# ADCIN_ACcoupled_ADT1-1WT.net
KiCad netlist of a schematic drawn in Altium Designer
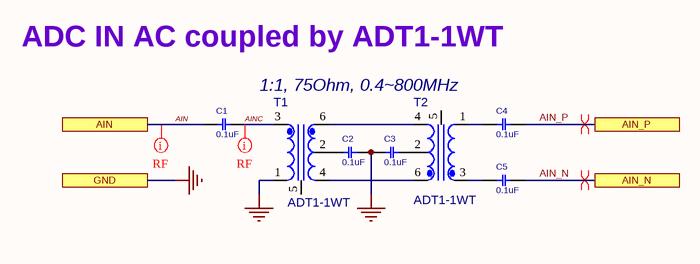
[diagram p0: ADCIN_ACcoupled_ADT1-1WT.SchDoc]

(export (version "E")
  (design (tool "Eeschema 10.0.6"))
  (components
    (comp (ref "C1")
      (value "0.1uF")
      (footprint "C0402")
      (description "CAP, MLCC, 100nF, 50V, X7R, 10%, 0402C")
      (fields (field (name "MANF_P#") "GCM155R71H104KE02D") (field (name "MANF") "Murata"))
      (libsource (lib "mlcc_smd_passive") (part "CAP_SMD_MLCC_100n50TDK"))
    )
    (comp (ref "C2")
      (value "0.1uF")
      (footprint "C0402")
      (description "CAP, MLCC, 100nF, 50V, X7R, 10%, 0402C")
      (fields (field (name "MANF_P#") "GCM155R71H104KE02D") (field (name "MANF") "Murata"))
      (libsource (lib "mlcc_smd_passive") (part "CAP_SMD_MLCC_100n50TDK"))
    )
    (comp (ref "C3")
      (value "0.1uF")
      (footprint "C0402")
      (description "CAP, MLCC, 100nF, 50V, X7R, 10%, 0402C")
      (fields (field (name "MANF_P#") "GCM155R71H104KE02D") (field (name "MANF") "Murata"))
      (libsource (lib "mlcc_smd_passive") (part "CAP_SMD_MLCC_100n50TDK"))
    )
    (comp (ref "C4")
      (value "0.1uF")
      (footprint "C0402")
      (description "CAP, MLCC, 100nF, 50V, X7R, 10%, 0402C")
      (fields (field (name "MANF_P#") "GCM155R71H104KE02D") (field (name "MANF") "Murata"))
      (libsource (lib "mlcc_smd_passive") (part "CAP_SMD_MLCC_100n50TDK"))
    )
    (comp (ref "C5")
      (value "0.1uF")
      (footprint "C0402")
      (description "CAP, MLCC, 100nF, 50V, X7R, 10%, 0402C")
      (fields (field (name "MANF_P#") "GCM155R71H104KE02D") (field (name "MANF") "Murata"))
      (libsource (lib "mlcc_smd_passive") (part "CAP_SMD_MLCC_100n50TDK"))
    )
    (comp (ref "T1")
      (value "ADT1-1WT")
      (footprint "TRNS254_6_8X6")
      (description "RF Transformer, 1:1, 75Ohm, 0.4~800MHz")
      (fields (field (name "MANF") "Mini-Circuits") (field (name "MANF_P#") "ADT1-1WT, ADT1-1WT+"))
      (libsource (lib "transformer_rf") (part "ADT1-1WT"))
    )
    (comp (ref "T2")
      (value "ADT1-1WT")
      (footprint "TRNS254_6_8X6")
      (description "RF Transformer, 1:1, 75Ohm, 0.4~800MHz")
      (fields (field (name "MANF") "Mini-Circuits") (field (name "MANF_P#") "ADT1-1WT, ADT1-1WT+"))
      (libsource (lib "transformer_rf") (part "ADT1-1WT"))
    )
  )
  (nets
    (net (code "1") (name "/AIN") (class "Default")
      (node (ref "C1") (pin "1") (pinfunction "1_1") (pintype "passive"))
    )
    (net (code "2") (name "/AINC") (class "Default")
      (node (ref "C1") (pin "2") (pinfunction "2_2") (pintype "passive"))
      (node (ref "T1") (pin "3") (pinfunction "PRI_DOT_3") (pintype "passive"))
    )
    (net (code "3") (name "/AIN_N") (class "Default")
      (node (ref "C5") (pin "2") (pinfunction "2_2") (pintype "passive"))
    )
    (net (code "4") (name "/AIN_P") (class "Default")
      (node (ref "C4") (pin "2") (pinfunction "2_2") (pintype "passive"))
    )
    (net (code "5") (name "GND") (class "Default")
      (node (ref "C2") (pin "2") (pinfunction "2_2") (pintype "passive"))
      (node (ref "C3") (pin "1") (pinfunction "1_1") (pintype "passive"))
      (node (ref "T1") (pin "1") (pinfunction "PRI_1") (pintype "passive"))
    )
    (net (code "6") (name "Net-(T1-SEC)") (class "Default")
      (node (ref "T1") (pin "4") (pinfunction "SEC_4") (pintype "passive"))
      (node (ref "T2") (pin "6") (pinfunction "SEC_DOT_6") (pintype "passive"))
    )
    (net (code "7") (name "Net-(T1-SEC_CT)") (class "Default")
      (node (ref "C2") (pin "1") (pinfunction "1_1") (pintype "passive"))
      (node (ref "T1") (pin "2") (pinfunction "SEC_CT_2") (pintype "passive"))
    )
    (net (code "8") (name "Net-(T1-SEC_DOT)") (class "Default")
      (node (ref "T1") (pin "6") (pinfunction "SEC_DOT_6") (pintype "passive"))
      (node (ref "T2") (pin "4") (pinfunction "SEC_4") (pintype "passive"))
    )
    (net (code "9") (name "Net-(T2-PRI)") (class "Default")
      (node (ref "C4") (pin "1") (pinfunction "1_1") (pintype "passive"))
      (node (ref "T2") (pin "1") (pinfunction "PRI_1") (pintype "passive"))
    )
    (net (code "10") (name "Net-(T2-PRI_DOT)") (class "Default")
      (node (ref "C5") (pin "1") (pinfunction "1_1") (pintype "passive"))
      (node (ref "T2") (pin "3") (pinfunction "PRI_DOT_3") (pintype "passive"))
    )
    (net (code "11") (name "Net-(T2-SEC_CT)") (class "Default")
      (node (ref "C3") (pin "2") (pinfunction "2_2") (pintype "passive"))
      (node (ref "T2") (pin "2") (pinfunction "SEC_CT_2") (pintype "passive"))
    )
    (net (code "12") (name "unconnected-(T1-NC-Pad5)") (class "Default")
      (node (ref "T1") (pin "5") (pinfunction "NC_5") (pintype "passive"))
    )
    (net (code "13") (name "unconnected-(T2-NC-Pad5)") (class "Default")
      (node (ref "T2") (pin "5") (pinfunction "NC_5") (pintype "passive"))
    )
  )
)
